# 5V_Power_Supply.net
KiCad netlist of a schematic drawn in Altium Designer
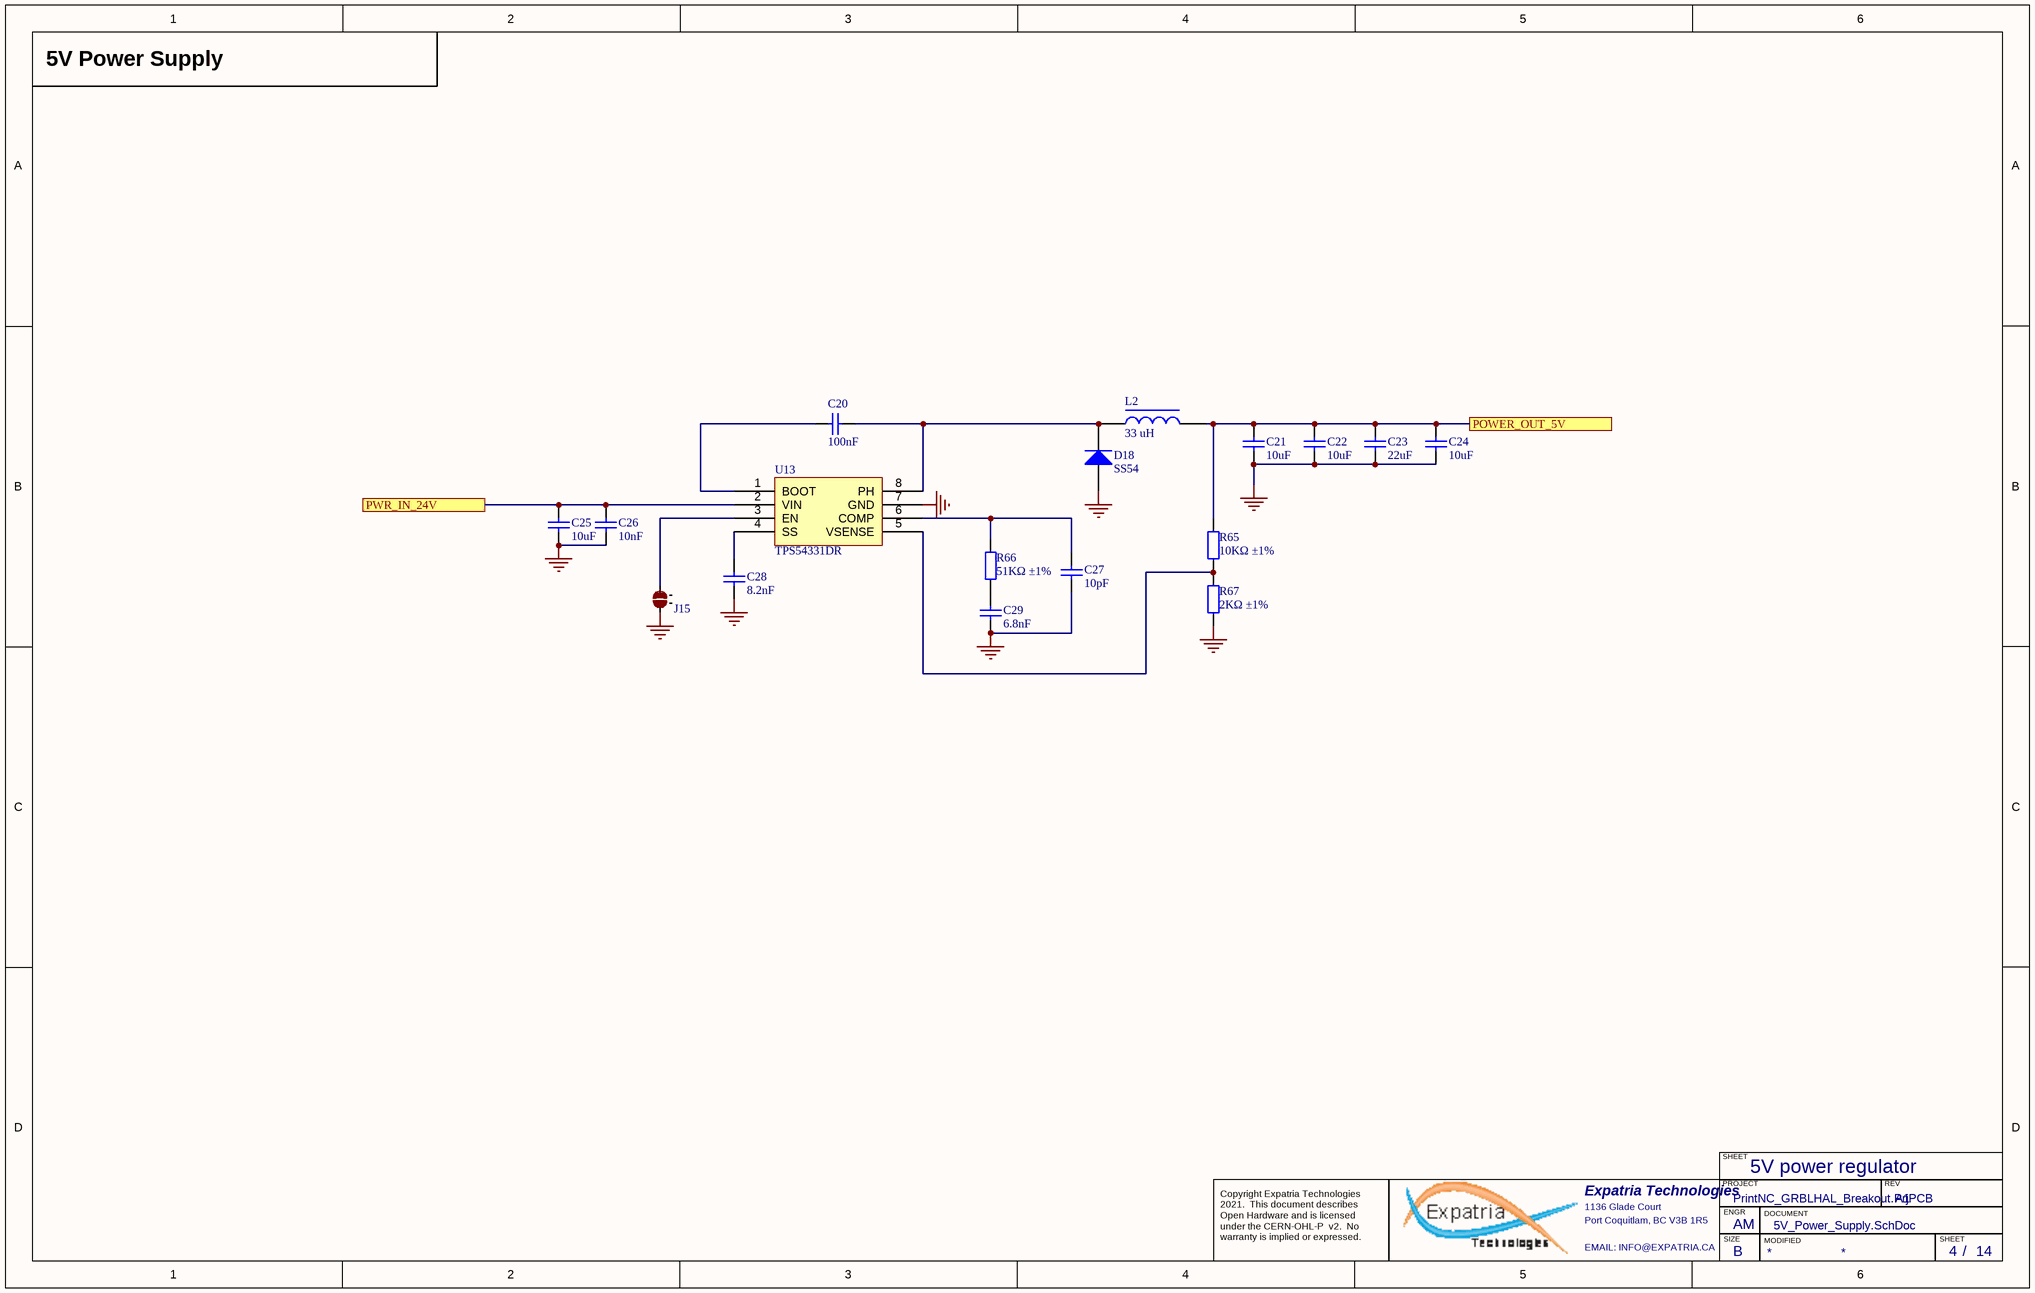
[diagram p0: 5V_Power_Supply.SchDoc]

(export (version "E")
  (design (tool "Eeschema 10.0.6"))
  (components
    (comp (ref "C20")
      (value "100nF")
      (footprint "0603_C")
      (description "Chip capacitors")
      (fields (field (name "MANUFACTURER") "YAGEO") (field (name "PARTNUMBER") "CC0603KRX7R9BB104"))
      (libsource (lib "Cap") (part "0603 100nF (104) 10% 50V"))
    )
    (comp (ref "C21")
      (value "10uF")
      (footprint "0603_C")
      (description "Chip capacitors")
      (fields
        (field (name "MANUFACTURER") "Samsung Electro-Mechanics")
        (field (name "PARTNUMBER") "CL10A106KP8NNNC")
      )
      (libsource (lib "Cap") (part "0603 10uF (106) 10% 10V"))
    )
    (comp (ref "C22")
      (value "10uF")
      (footprint "0603_C")
      (description "Chip capacitors")
      (fields
        (field (name "MANUFACTURER") "Samsung Electro-Mechanics")
        (field (name "PARTNUMBER") "CL10A106KP8NNNC")
      )
      (libsource (lib "Cap") (part "0603 10uF (106) 10% 10V"))
    )
    (comp (ref "C23")
      (value "22uF")
      (footprint "0805_C")
      (description "Chip capacitors")
      (fields
        (field (name "MANUFACTURER") "Samsung Electro-Mechanics")
        (field (name "PARTNUMBER") "CL21A226MAQNNNE")
      )
      (libsource (lib "Cap") (part "0805 22uF (226) 20% 25V"))
    )
    (comp (ref "C24")
      (value "10uF")
      (footprint "0603_C")
      (description "Chip capacitors")
      (fields
        (field (name "MANUFACTURER") "Samsung Electro-Mechanics")
        (field (name "PARTNUMBER") "CL10A106KP8NNNC")
      )
      (libsource (lib "Cap") (part "0603 10uF (106) 10% 10V"))
    )
    (comp (ref "C25")
      (value "10uF")
      (footprint "1206_C")
      (description "Chip capacitors")
      (fields
        (field (name "MANUFACTURER") "Samsung Electro-Mechanics")
        (field (name "PARTNUMBER") "CL31A106KBHNNNE")
      )
      (libsource (lib "Cap") (part "1206 10uF (106) 10% 50V"))
    )
    (comp (ref "C26")
      (value "10nF")
      (footprint "0402_C")
      (description "Chip capacitors")
      (fields
        (field (name "MANUFACTURER") "Samsung Electro-Mechanics")
        (field (name "PARTNUMBER") "CL05B103KB5NNNC")
      )
      (libsource (lib "Cap") (part "0402 10nF (103) 10% 50V"))
    )
    (comp (ref "C27")
      (value "10pF")
      (footprint "0402_C")
      (description "Chip capacitors")
      (fields
        (field (name "MANUFACTURER") "Samsung Electro-Mechanics")
        (field (name "PARTNUMBER") "CL05C100JB5NNNC")
      )
      (libsource (lib "Cap") (part "0402 10pF (100) 5% 50V"))
    )
    (comp (ref "C28")
      (value "8.2nF")
      (footprint "0603_C")
      (description "Chip capacitors")
      (fields
        (field (name "MANUFACTURER") "Samsung Electro-Mechanics")
        (field (name "PARTNUMBER") "CL10B822KB8NNNC")
      )
      (libsource (lib "Cap") (part "0603 8.2nF (822) 10% 50V"))
    )
    (comp (ref "C29")
      (value "6.8nF")
      (footprint "0402_C")
      (description "Chip capacitors")
      (fields
        (field (name "MANUFACTURER") "Guangdong Fenghua Advanced Tech")
        (field (name "PARTNUMBER") "0402B682K500NT")
      )
      (libsource (lib "Cap") (part "0402 6.8nF (682) 10% 50V"))
    )
    (comp (ref "D18")
      (value "SS54")
      (footprint "SMA(DO-214AC)_S1")
      (description "二极管")
      (libsource (lib "Diode") (part "SMA(DO-214AC) SS54"))
    )
    (comp (ref "J15")
      (value "2 way net solder junction - Normally Open")
      (footprint "2waySolder_NO")
      (libsource (lib "PrintNC_GRBLHAL_Breakout") (part "2waySolderNO"))
    )
    (comp (ref "L2")
      (value "33 uH")
      (footprint "INDPM7366X300N")
      (description "33uH ±20% 2A 270mΩ SMD,6.6x7.3x3.0mm Power Inductors RoHS")
      (libsource (lib "PrintNC_GRBLHAL_Breakout") (part "1206 10uH 10%"))
    )
    (comp (ref "R65")
      (value "10KΩ ±1%")
      (footprint "0402_R")
      (description "Chip resistor")
      (fields (field (name "MANUFACTURER") "Uniroyal Elec") (field (name "PARTNUMBER") "0402WGF1002TCE"))
      (libsource (lib "PrintNC_GRBLHAL_Breakout") (part "0402 10K (1002) 1%"))
    )
    (comp (ref "R66")
      (value "51KΩ ±1%")
      (footprint "0402_R")
      (description "Chip resistor")
      (fields (field (name "MANUFACTURER") "Uniroyal Elec") (field (name "PARTNUMBER") "0402WGF5102TCE"))
      (libsource (lib "PrintNC_GRBLHAL_Breakout") (part "0402 51K (5102) 1%"))
    )
    (comp (ref "R67")
      (value "2KΩ ±1%")
      (footprint "0402_R")
      (description "Chip resistor")
      (fields (field (name "MANUFACTURER") "Uniroyal Elec") (field (name "PARTNUMBER") "0402WGF2001TCE"))
      (libsource (lib "PrintNC_GRBLHAL_Breakout") (part "0402 2K (2001) 1%"))
    )
    (comp (ref "U13")
      (value "TPS54331DR")
      (footprint "SOIC-8_150mil")
      (description "DC-DC芯片")
      (libsource (lib "PrintNC_GRBLHAL_Breakout") (part "TPS54331DR_[C9865]"))
    )
  )
  (nets
    (net (code "1") (name "/POWER_OUT_5V") (class "Default")
      (node (ref "C21") (pin "2") (pinfunction "2_2") (pintype "passive"))
      (node (ref "C22") (pin "2") (pinfunction "2_2") (pintype "passive"))
      (node (ref "C23") (pin "2") (pinfunction "2_2") (pintype "passive"))
      (node (ref "C24") (pin "2") (pinfunction "2_2") (pintype "passive"))
      (node (ref "L2") (pin "2") (pinfunction "2_2") (pintype "passive"))
      (node (ref "R65") (pin "2") (pinfunction "2_2") (pintype "passive"))
    )
    (net (code "2") (name "/PWR_IN_24V") (class "Default")
      (node (ref "C25") (pin "2") (pinfunction "2_2") (pintype "passive"))
      (node (ref "C26") (pin "2") (pinfunction "2_2") (pintype "passive"))
      (node (ref "U13") (pin "2") (pinfunction "VIN_2") (pintype "passive"))
    )
    (net (code "3") (name "GND") (class "Default")
      (node (ref "C21") (pin "1") (pinfunction "1_1") (pintype "passive"))
      (node (ref "C22") (pin "1") (pinfunction "1_1") (pintype "passive"))
      (node (ref "C23") (pin "1") (pinfunction "1_1") (pintype "passive"))
      (node (ref "C24") (pin "1") (pinfunction "1_1") (pintype "passive"))
      (node (ref "C25") (pin "1") (pinfunction "1_1") (pintype "passive"))
      (node (ref "C26") (pin "1") (pinfunction "1_1") (pintype "passive"))
      (node (ref "C27") (pin "1") (pinfunction "1_1") (pintype "passive"))
      (node (ref "C28") (pin "1") (pinfunction "1_1") (pintype "passive"))
      (node (ref "C29") (pin "1") (pinfunction "1_1") (pintype "passive"))
      (node (ref "D18") (pin "1") (pinfunction "A_1") (pintype "passive"))
      (node (ref "J15") (pin "1") (pinfunction "1_1") (pintype "passive"))
      (node (ref "R67") (pin "1") (pinfunction "1_1") (pintype "passive"))
      (node (ref "U13") (pin "7") (pinfunction "GND_7") (pintype "passive"))
    )
    (net (code "4") (name "Net-(C29-Pad2)") (class "Default")
      (node (ref "C29") (pin "2") (pinfunction "2_2") (pintype "passive"))
      (node (ref "R66") (pin "1") (pinfunction "1_1") (pintype "passive"))
    )
    (net (code "5") (name "Net-(D18-K)") (class "Default")
      (node (ref "C20") (pin "2") (pinfunction "2_2") (pintype "passive"))
      (node (ref "D18") (pin "2") (pinfunction "K_2") (pintype "passive"))
      (node (ref "L2") (pin "1") (pinfunction "1_1") (pintype "passive"))
      (node (ref "U13") (pin "8") (pinfunction "PH_8") (pintype "passive"))
    )
    (net (code "6") (name "Net-(U13-BOOT)") (class "Default")
      (node (ref "C20") (pin "1") (pinfunction "1_1") (pintype "passive"))
      (node (ref "U13") (pin "1") (pinfunction "BOOT_1") (pintype "passive"))
    )
    (net (code "7") (name "Net-(U13-COMP)") (class "Default")
      (node (ref "C27") (pin "2") (pinfunction "2_2") (pintype "passive"))
      (node (ref "R66") (pin "2") (pinfunction "2_2") (pintype "passive"))
      (node (ref "U13") (pin "6") (pinfunction "COMP_6") (pintype "passive"))
    )
    (net (code "8") (name "Net-(U13-EN)") (class "Default")
      (node (ref "J15") (pin "2") (pinfunction "2_2") (pintype "passive"))
      (node (ref "U13") (pin "3") (pinfunction "EN_3") (pintype "passive"))
    )
    (net (code "9") (name "Net-(U13-SS)") (class "Default")
      (node (ref "C28") (pin "2") (pinfunction "2_2") (pintype "passive"))
      (node (ref "U13") (pin "4") (pinfunction "SS_4") (pintype "passive"))
    )
    (net (code "10") (name "Net-(U13-VSENSE)") (class "Default")
      (node (ref "R65") (pin "1") (pinfunction "1_1") (pintype "passive"))
      (node (ref "R67") (pin "2") (pinfunction "2_2") (pintype "passive"))
      (node (ref "U13") (pin "5") (pinfunction "VSENSE_5") (pintype "passive"))
    )
  )
)
